# SAI_POWER_SUPPLY_BOARD.net
KiCad netlist of a schematic drawn in EAGLE
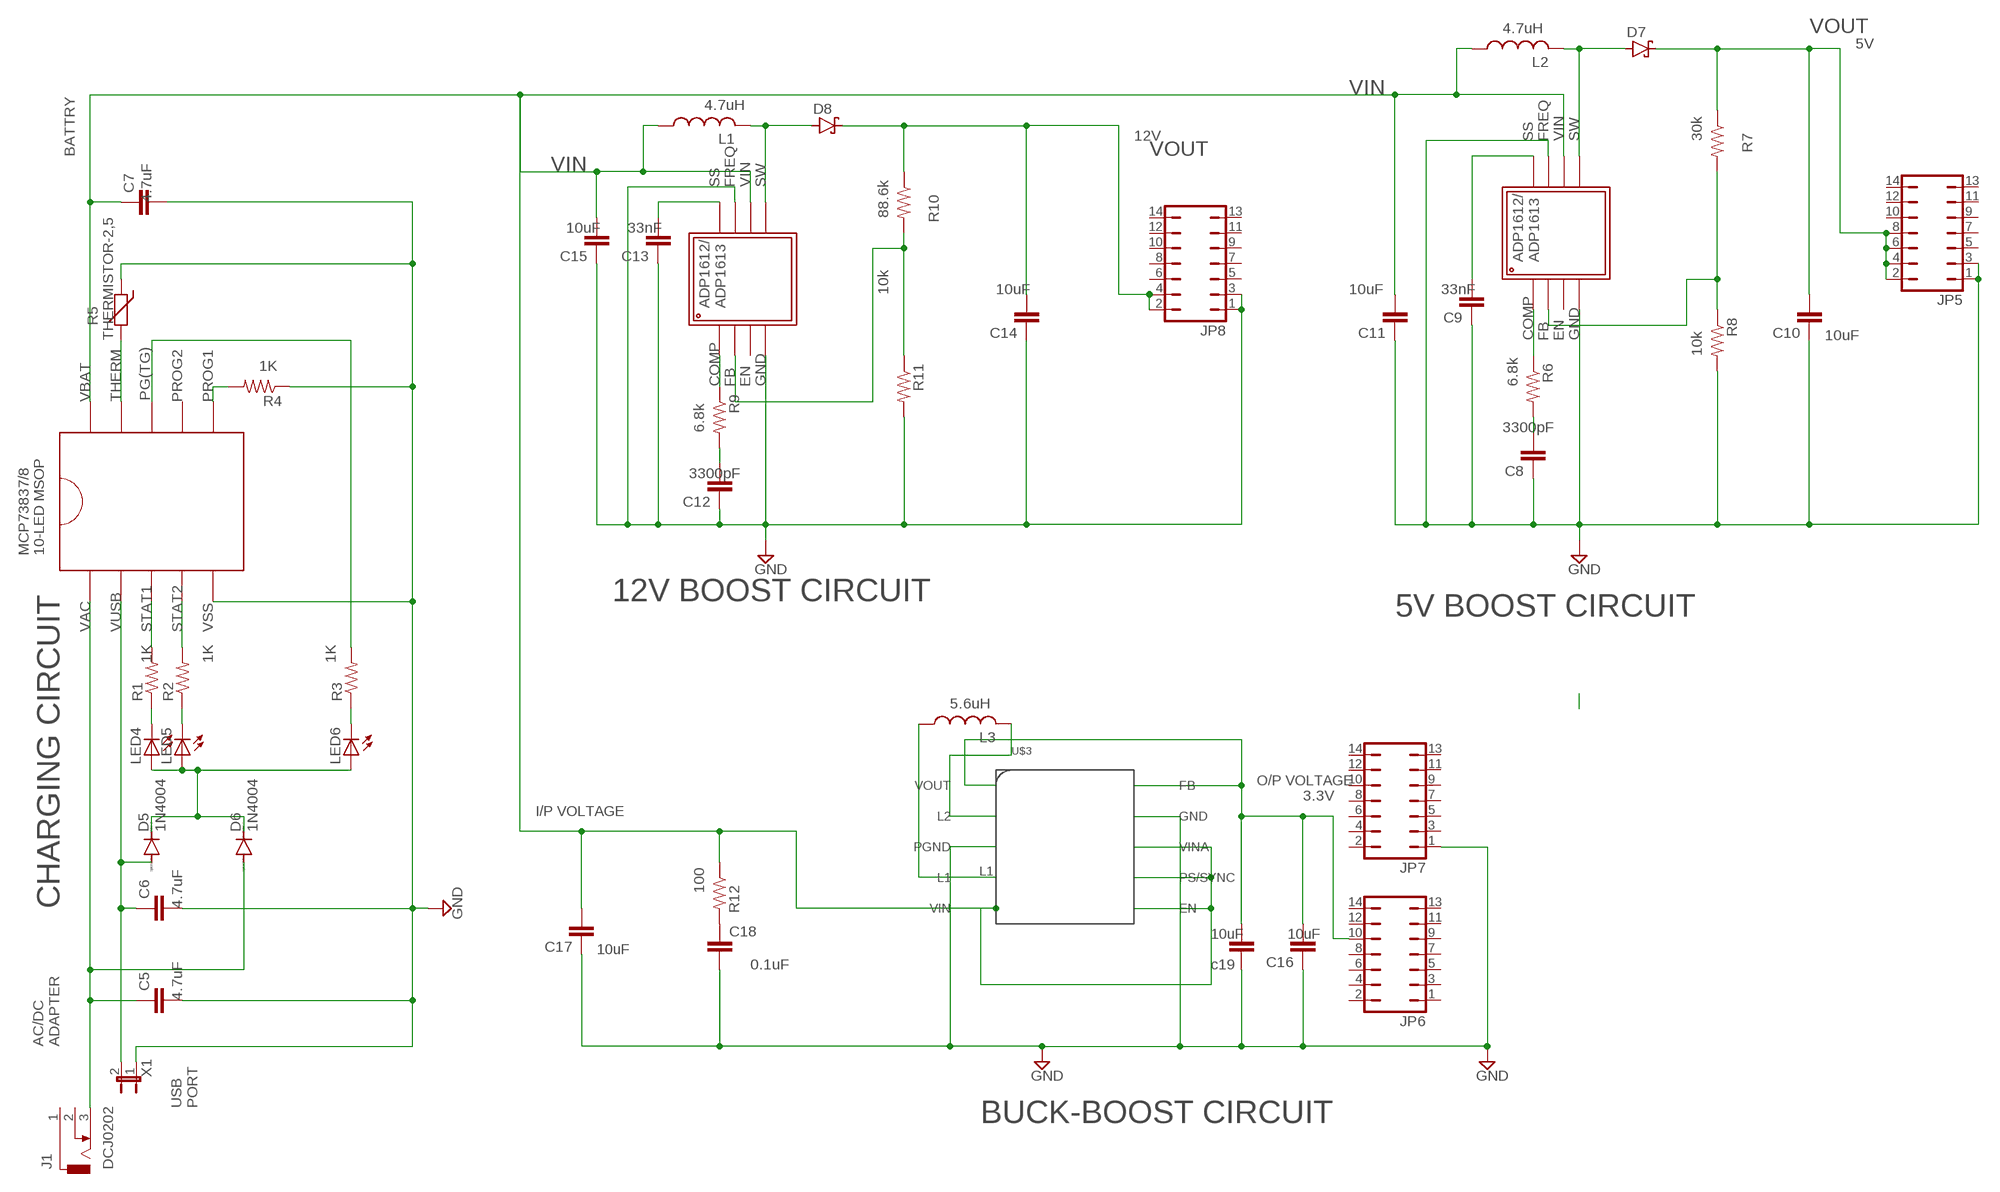
[diagram p0: schematic, sheet 1]

(export (version "E")
  (design (tool "Eeschema 10.0.6"))
  (components
    (comp (ref "C1")
      (value "C2,5-3")
      (footprint "eagle-import:C2.5-3")
      (libsource (lib "eagle-import") (part "C2,5-3"))
    )
    (comp (ref "C5")
      (value "C2.5/5")
      (footprint "eagle-import:C2.5-5")
      (libsource (lib "eagle-import") (part "C2.5/5"))
    )
    (comp (ref "C6")
      (value "C2.5/5")
      (footprint "eagle-import:C2.5-5")
      (libsource (lib "eagle-import") (part "C2.5/5"))
    )
    (comp (ref "C7")
      (value "C2.5/5")
      (footprint "eagle-import:C2.5-5")
      (libsource (lib "eagle-import") (part "C2.5/5"))
    )
    (comp (ref "C8")
      (value "C2,5-3")
      (footprint "eagle-import:C2.5-3")
      (libsource (lib "eagle-import") (part "C2,5-3"))
    )
    (comp (ref "C9")
      (value "C2,5-3")
      (footprint "eagle-import:C2.5-3")
      (libsource (lib "eagle-import") (part "C2,5-3"))
    )
    (comp (ref "C10")
      (value "C2,5-3")
      (footprint "eagle-import:C2.5-3")
      (libsource (lib "eagle-import") (part "C2,5-3"))
    )
    (comp (ref "C11")
      (value "C2,5-3")
      (footprint "eagle-import:C2.5-3")
      (libsource (lib "eagle-import") (part "C2,5-3"))
    )
    (comp (ref "C12")
      (value "C2,5-3")
      (footprint "eagle-import:C2.5-3")
      (libsource (lib "eagle-import") (part "C2,5-3"))
    )
    (comp (ref "C13")
      (value "C2,5-3")
      (footprint "eagle-import:C2.5-3")
      (libsource (lib "eagle-import") (part "C2,5-3"))
    )
    (comp (ref "C14")
      (value "C2,5-3")
      (footprint "eagle-import:C2.5-3")
      (libsource (lib "eagle-import") (part "C2,5-3"))
    )
    (comp (ref "C15")
      (value "C2,5-3")
      (footprint "eagle-import:C2.5-3")
      (libsource (lib "eagle-import") (part "C2,5-3"))
    )
    (comp (ref "C16")
      (value "C2,5-3")
      (footprint "eagle-import:C2.5-3")
      (libsource (lib "eagle-import") (part "C2,5-3"))
    )
    (comp (ref "C17")
      (value "C2,5-3")
      (footprint "eagle-import:C2.5-3")
      (libsource (lib "eagle-import") (part "C2,5-3"))
    )
    (comp (ref "C18")
      (value "C2,5-3")
      (footprint "eagle-import:C2.5-3")
      (libsource (lib "eagle-import") (part "C2,5-3"))
    )
    (comp (ref "D5")
      (value "1N4004")
      (footprint "eagle-import:DO41-10")
      (libsource (lib "eagle-import") (part "1N4004"))
    )
    (comp (ref "D6")
      (value "1N4004")
      (footprint "eagle-import:DO41-10")
      (libsource (lib "eagle-import") (part "1N4004"))
    )
    (comp (ref "D7")
      (value "SCHOTTKY-DIODEC4111-15")
      (footprint "eagle-import:C4111-15")
      (libsource (lib "eagle-import") (part "SCHOTTKY-DIODEC4111-15"))
    )
    (comp (ref "D8")
      (value "SCHOTTKY-DIODEC4111-15")
      (footprint "eagle-import:C4111-15")
      (libsource (lib "eagle-import") (part "SCHOTTKY-DIODEC4111-15"))
    )
    (comp (ref "J1")
      (value "DCJ0202")
      (footprint "eagle-import:DCJ0202")
      (libsource (lib "eagle-import") (part "DCJ0202"))
    )
    (comp (ref "JP1")
      (value "JP1E")
      (footprint "eagle-import:JP1")
      (libsource (lib "eagle-import") (part "JP1E"))
    )
    (comp (ref "JP5")
      (value "JP7Q")
      (footprint "eagle-import:JP7Q")
      (libsource (lib "eagle-import") (part "JP7Q"))
    )
    (comp (ref "JP6")
      (value "JP7Q")
      (footprint "eagle-import:JP7Q")
      (libsource (lib "eagle-import") (part "JP7Q"))
    )
    (comp (ref "JP7")
      (value "JP7Q")
      (footprint "eagle-import:JP7Q")
      (libsource (lib "eagle-import") (part "JP7Q"))
    )
    (comp (ref "JP8")
      (value "JP7Q")
      (footprint "eagle-import:JP7Q")
      (libsource (lib "eagle-import") (part "JP7Q"))
    )
    (comp (ref "L1")
      (value "L-US0204/5")
      (footprint "eagle-import:0204_5")
      (libsource (lib "eagle-import") (part "L-US0204/5"))
    )
    (comp (ref "L2")
      (value "L-US0204/5")
      (footprint "eagle-import:0204_5")
      (libsource (lib "eagle-import") (part "L-US0204/5"))
    )
    (comp (ref "L3")
      (value "L-US0204/5")
      (footprint "eagle-import:0204_5")
      (libsource (lib "eagle-import") (part "L-US0204/5"))
    )
    (comp (ref "LED4")
      (value "LED3MM")
      (footprint "eagle-import:LED3MM")
      (libsource (lib "eagle-import") (part "LED3MM"))
    )
    (comp (ref "LED5")
      (value "LED3MM")
      (footprint "eagle-import:LED3MM")
      (libsource (lib "eagle-import") (part "LED3MM"))
    )
    (comp (ref "LED6")
      (value "LED3MM")
      (footprint "eagle-import:LED3MM")
      (libsource (lib "eagle-import") (part "LED3MM"))
    )
    (comp (ref "R1")
      (value "R-US_0204/2V")
      (footprint "eagle-import:0204V")
      (libsource (lib "eagle-import") (part "R-US_0204/2V"))
    )
    (comp (ref "R2")
      (value "R-US_0204/2V")
      (footprint "eagle-import:0204V")
      (libsource (lib "eagle-import") (part "R-US_0204/2V"))
    )
    (comp (ref "R3")
      (value "R-US_0204/2V")
      (footprint "eagle-import:0204V")
      (libsource (lib "eagle-import") (part "R-US_0204/2V"))
    )
    (comp (ref "R4")
      (value "R-US_0204/2V")
      (footprint "eagle-import:0204V")
      (libsource (lib "eagle-import") (part "R-US_0204/2V"))
    )
    (comp (ref "R5")
      (value "THERMISTOR-2,5")
      (footprint "eagle-import:RS-2,5")
      (libsource (lib "eagle-import") (part "THERMISTOR-2,5"))
    )
    (comp (ref "R6")
      (value "R-US_0204/2V")
      (footprint "eagle-import:0204V")
      (libsource (lib "eagle-import") (part "R-US_0204/2V"))
    )
    (comp (ref "R7")
      (value "R-US_0204/2V")
      (footprint "eagle-import:0204V")
      (libsource (lib "eagle-import") (part "R-US_0204/2V"))
    )
    (comp (ref "R8")
      (value "R-US_0204/2V")
      (footprint "eagle-import:0204V")
      (libsource (lib "eagle-import") (part "R-US_0204/2V"))
    )
    (comp (ref "R9")
      (value "R-US_0204/2V")
      (footprint "eagle-import:0204V")
      (libsource (lib "eagle-import") (part "R-US_0204/2V"))
    )
    (comp (ref "R10")
      (value "R-US_0204/2V")
      (footprint "eagle-import:0204V")
      (libsource (lib "eagle-import") (part "R-US_0204/2V"))
    )
    (comp (ref "R11")
      (value "R-US_0204/2V")
      (footprint "eagle-import:0204V")
      (libsource (lib "eagle-import") (part "R-US_0204/2V"))
    )
    (comp (ref "R12")
      (value "R-US_0204/2V")
      (footprint "eagle-import:0204V")
      (libsource (lib "eagle-import") (part "R-US_0204/2V"))
    )
    (comp (ref "U$1")
      (value "ADP1612")
      (footprint "eagle-import:ADP1612")
      (libsource (lib "eagle-import") (part "ADP1612"))
    )
    (comp (ref "U$2")
      (value "ADP1612")
      (footprint "eagle-import:ADP1612")
      (libsource (lib "eagle-import") (part "ADP1612"))
    )
    (comp (ref "U$3")
      (value "TPS63002")
      (footprint "eagle-import:TPS63002")
      (libsource (lib "eagle-import") (part "TPS63002"))
    )
    (comp (ref "U$4")
      (value "MCP73837/8")
      (footprint "eagle-import:MCP73837_8")
      (libsource (lib "eagle-import") (part "MCP73837/8"))
    )
  )
  (nets
    (net (code "1") (name "GND") (class "Default")
      (node (ref "C1") (pin "1") (pinfunction "1_1") (pintype "passive"))
      (node (ref "C10") (pin "1") (pinfunction "1_1") (pintype "passive"))
      (node (ref "C11") (pin "1") (pinfunction "1_1") (pintype "passive"))
      (node (ref "C12") (pin "1") (pinfunction "1_1") (pintype "passive"))
      (node (ref "C13") (pin "1") (pinfunction "1_1") (pintype "passive"))
      (node (ref "C14") (pin "1") (pinfunction "1_1") (pintype "passive"))
      (node (ref "C15") (pin "1") (pinfunction "1_1") (pintype "passive"))
      (node (ref "C16") (pin "1") (pinfunction "1_1") (pintype "passive"))
      (node (ref "C17") (pin "1") (pinfunction "1_1") (pintype "passive"))
      (node (ref "C18") (pin "2") (pinfunction "2_2") (pintype "passive"))
      (node (ref "C5") (pin "2") (pinfunction "2_2") (pintype "passive"))
      (node (ref "C6") (pin "2") (pinfunction "2_2") (pintype "passive"))
      (node (ref "C7") (pin "2") (pinfunction "2_2") (pintype "passive"))
      (node (ref "C8") (pin "1") (pinfunction "1_1") (pintype "passive"))
      (node (ref "C9") (pin "1") (pinfunction "1_1") (pintype "passive"))
      (node (ref "JP1") (pin "1") (pinfunction "1_1") (pintype "passive"))
      (node (ref "JP5") (pin "1") (pinfunction "1_1") (pintype "passive"))
      (node (ref "JP5") (pin "3") (pinfunction "3_3") (pintype "passive"))
      (node (ref "JP7") (pin "1") (pinfunction "1_1") (pintype "passive"))
      (node (ref "JP8") (pin "1") (pinfunction "1_1") (pintype "passive"))
      (node (ref "JP8") (pin "3") (pinfunction "3_3") (pintype "passive"))
      (node (ref "R11") (pin "2") (pinfunction "2_2") (pintype "passive"))
      (node (ref "R4") (pin "1") (pinfunction "1_1") (pintype "passive"))
      (node (ref "R5") (pin "1") (pinfunction "1_1") (pintype "passive"))
      (node (ref "R8") (pin "2") (pinfunction "2_2") (pintype "passive"))
      (node (ref "U$1") (pin "P$4") (pinfunction "P$4_P$4") (pintype "bidirectional"))
      (node (ref "U$1") (pin "P$6") (pinfunction "P$6_P$6") (pintype "bidirectional"))
      (node (ref "U$2") (pin "P$4") (pinfunction "P$4_P$4") (pintype "bidirectional"))
      (node (ref "U$2") (pin "P$6") (pinfunction "P$6_P$6") (pintype "bidirectional"))
      (node (ref "U$3") (pin "GND") (pinfunction "GND_GND") (pintype "bidirectional"))
      (node (ref "U$3") (pin "PGND") (pinfunction "PGND_PGND") (pintype "bidirectional"))
      (node (ref "U$4") (pin "P$5") (pinfunction "P$5_P$5") (pintype "bidirectional"))
    )
    (net (code "2") (name "Net-(C1-Pad2)") (class "Default")
      (node (ref "C1") (pin "2") (pinfunction "2_2") (pintype "passive"))
      (node (ref "C16") (pin "2") (pinfunction "2_2") (pintype "passive"))
      (node (ref "JP6") (pin "10") (pinfunction "10_10") (pintype "passive"))
      (node (ref "U$3") (pin "FB") (pinfunction "FB_FB") (pintype "bidirectional"))
      (node (ref "U$3") (pin "VOUT") (pinfunction "VOUT_VOUT") (pintype "bidirectional"))
    )
    (net (code "3") (name "Net-(C5-Pad1)") (class "Default")
      (node (ref "C5") (pin "1") (pinfunction "1_1") (pintype "passive"))
      (node (ref "D6") (pin "A") (pinfunction "A_A") (pintype "passive"))
      (node (ref "J1") (pin "3") (pinfunction "3_3") (pintype "passive"))
      (node (ref "U$4") (pin "P$1") (pinfunction "P$1_P$1") (pintype "bidirectional"))
    )
    (net (code "4") (name "Net-(C6-Pad1)") (class "Default")
      (node (ref "C6") (pin "1") (pinfunction "1_1") (pintype "passive"))
      (node (ref "D5") (pin "A") (pinfunction "A_A") (pintype "passive"))
      (node (ref "JP1") (pin "2") (pinfunction "2_2") (pintype "passive"))
      (node (ref "U$4") (pin "P$2") (pinfunction "P$2_P$2") (pintype "bidirectional"))
    )
    (net (code "5") (name "Net-(C8-Pad2)") (class "Default")
      (node (ref "C8") (pin "2") (pinfunction "2_2") (pintype "passive"))
      (node (ref "R6") (pin "2") (pinfunction "2_2") (pintype "passive"))
    )
    (net (code "6") (name "Net-(C9-Pad2)") (class "Default")
      (node (ref "C9") (pin "2") (pinfunction "2_2") (pintype "passive"))
      (node (ref "U$1") (pin "P$5") (pinfunction "P$5_P$5") (pintype "bidirectional"))
    )
    (net (code "7") (name "Net-(C10-Pad2)") (class "Default")
      (node (ref "C10") (pin "2") (pinfunction "2_2") (pintype "passive"))
      (node (ref "D7") (pin "C") (pinfunction "C_C") (pintype "passive"))
      (node (ref "JP5") (pin "2") (pinfunction "2_2") (pintype "passive"))
      (node (ref "JP5") (pin "4") (pinfunction "4_4") (pintype "passive"))
      (node (ref "JP5") (pin "6") (pinfunction "6_6") (pintype "passive"))
      (node (ref "JP5") (pin "8") (pinfunction "8_8") (pintype "passive"))
      (node (ref "R7") (pin "1") (pinfunction "1_1") (pintype "passive"))
    )
    (net (code "8") (name "Net-(C11-Pad2)") (class "Default")
      (node (ref "C11") (pin "2") (pinfunction "2_2") (pintype "passive"))
      (node (ref "C15") (pin "2") (pinfunction "2_2") (pintype "passive"))
      (node (ref "C17") (pin "2") (pinfunction "2_2") (pintype "passive"))
      (node (ref "C7") (pin "1") (pinfunction "1_1") (pintype "passive"))
      (node (ref "L1") (pin "1") (pinfunction "1_1") (pintype "passive"))
      (node (ref "L2") (pin "1") (pinfunction "1_1") (pintype "passive"))
      (node (ref "R12") (pin "1") (pinfunction "1_1") (pintype "passive"))
      (node (ref "U$1") (pin "P$7") (pinfunction "P$7_P$7") (pintype "bidirectional"))
      (node (ref "U$2") (pin "P$7") (pinfunction "P$7_P$7") (pintype "bidirectional"))
      (node (ref "U$3") (pin "EN") (pinfunction "EN_EN") (pintype "bidirectional"))
      (node (ref "U$3") (pin "PS/SYNC") (pinfunction "PS/SYNC_PS/SYNC") (pintype "bidirectional"))
      (node (ref "U$3") (pin "VIN") (pinfunction "VIN_VIN") (pintype "bidirectional"))
      (node (ref "U$3") (pin "VINA") (pinfunction "VINA_VINA") (pintype "bidirectional"))
      (node (ref "U$4") (pin "P$10") (pinfunction "P$10_P$10") (pintype "bidirectional"))
    )
    (net (code "9") (name "Net-(C12-Pad2)") (class "Default")
      (node (ref "C12") (pin "2") (pinfunction "2_2") (pintype "passive"))
      (node (ref "R9") (pin "2") (pinfunction "2_2") (pintype "passive"))
    )
    (net (code "10") (name "Net-(C13-Pad2)") (class "Default")
      (node (ref "C13") (pin "2") (pinfunction "2_2") (pintype "passive"))
      (node (ref "U$2") (pin "P$5") (pinfunction "P$5_P$5") (pintype "bidirectional"))
    )
    (net (code "11") (name "Net-(C14-Pad2)") (class "Default")
      (node (ref "C14") (pin "2") (pinfunction "2_2") (pintype "passive"))
      (node (ref "D8") (pin "C") (pinfunction "C_C") (pintype "passive"))
      (node (ref "JP8") (pin "2") (pinfunction "2_2") (pintype "passive"))
      (node (ref "JP8") (pin "4") (pinfunction "4_4") (pintype "passive"))
      (node (ref "R10") (pin "1") (pinfunction "1_1") (pintype "passive"))
    )
    (net (code "12") (name "Net-(C18-Pad1)") (class "Default")
      (node (ref "C18") (pin "1") (pinfunction "1_1") (pintype "passive"))
      (node (ref "R12") (pin "2") (pinfunction "2_2") (pintype "passive"))
    )
    (net (code "13") (name "Net-(D5-PadC)") (class "Default")
      (node (ref "D5") (pin "C") (pinfunction "C_C") (pintype "passive"))
      (node (ref "D6") (pin "C") (pinfunction "C_C") (pintype "passive"))
      (node (ref "LED4") (pin "A") (pinfunction "A_A") (pintype "passive"))
      (node (ref "LED5") (pin "A") (pinfunction "A_A") (pintype "passive"))
      (node (ref "LED6") (pin "A") (pinfunction "A_A") (pintype "passive"))
    )
    (net (code "14") (name "Net-(D7-PadA)") (class "Default")
      (node (ref "D7") (pin "A") (pinfunction "A_A") (pintype "passive"))
      (node (ref "L2") (pin "2") (pinfunction "2_2") (pintype "passive"))
      (node (ref "U$1") (pin "P$8") (pinfunction "P$8_P$8") (pintype "bidirectional"))
    )
    (net (code "15") (name "Net-(D8-PadA)") (class "Default")
      (node (ref "D8") (pin "A") (pinfunction "A_A") (pintype "passive"))
      (node (ref "L1") (pin "2") (pinfunction "2_2") (pintype "passive"))
      (node (ref "U$2") (pin "P$8") (pinfunction "P$8_P$8") (pintype "bidirectional"))
    )
    (net (code "16") (name "Net-(L3-Pad1)") (class "Default")
      (node (ref "L3") (pin "1") (pinfunction "1_1") (pintype "passive"))
      (node (ref "U$3") (pin "L1") (pinfunction "L1_L1") (pintype "bidirectional"))
    )
    (net (code "17") (name "Net-(L3-Pad2)") (class "Default")
      (node (ref "L3") (pin "2") (pinfunction "2_2") (pintype "passive"))
      (node (ref "U$3") (pin "L2") (pinfunction "L2_L2") (pintype "bidirectional"))
    )
    (net (code "18") (name "Net-(LED4-C)") (class "Default")
      (node (ref "LED4") (pin "K") (pinfunction "C_K") (pintype "passive"))
      (node (ref "R1") (pin "1") (pinfunction "1_1") (pintype "passive"))
    )
    (net (code "19") (name "Net-(LED5-C)") (class "Default")
      (node (ref "LED5") (pin "K") (pinfunction "C_K") (pintype "passive"))
      (node (ref "R2") (pin "1") (pinfunction "1_1") (pintype "passive"))
    )
    (net (code "20") (name "Net-(LED6-C)") (class "Default")
      (node (ref "LED6") (pin "K") (pinfunction "C_K") (pintype "passive"))
      (node (ref "R3") (pin "1") (pinfunction "1_1") (pintype "passive"))
    )
    (net (code "21") (name "Net-(R1-Pad2)") (class "Default")
      (node (ref "R1") (pin "2") (pinfunction "2_2") (pintype "passive"))
      (node (ref "U$4") (pin "P$3") (pinfunction "P$3_P$3") (pintype "bidirectional"))
    )
    (net (code "22") (name "Net-(R2-Pad2)") (class "Default")
      (node (ref "R2") (pin "2") (pinfunction "2_2") (pintype "passive"))
      (node (ref "U$4") (pin "P$4") (pinfunction "P$4_P$4") (pintype "bidirectional"))
    )
    (net (code "23") (name "Net-(R3-Pad2)") (class "Default")
      (node (ref "R3") (pin "2") (pinfunction "2_2") (pintype "passive"))
      (node (ref "U$4") (pin "P$8") (pinfunction "P$8_P$8") (pintype "bidirectional"))
    )
    (net (code "24") (name "Net-(R4-Pad2)") (class "Default")
      (node (ref "R4") (pin "2") (pinfunction "2_2") (pintype "passive"))
      (node (ref "U$4") (pin "P$6") (pinfunction "P$6_P$6") (pintype "bidirectional"))
    )
    (net (code "25") (name "Net-(R5-Pad2)") (class "Default")
      (node (ref "R5") (pin "2") (pinfunction "2_2") (pintype "passive"))
      (node (ref "U$4") (pin "P$9") (pinfunction "P$9_P$9") (pintype "bidirectional"))
    )
    (net (code "26") (name "Net-(R6-Pad1)") (class "Default")
      (node (ref "R6") (pin "1") (pinfunction "1_1") (pintype "passive"))
      (node (ref "U$1") (pin "P$1") (pinfunction "P$1_P$1") (pintype "bidirectional"))
    )
    (net (code "27") (name "Net-(R7-Pad2)") (class "Default")
      (node (ref "R7") (pin "2") (pinfunction "2_2") (pintype "passive"))
      (node (ref "R8") (pin "1") (pinfunction "1_1") (pintype "passive"))
      (node (ref "U$1") (pin "P$2") (pinfunction "P$2_P$2") (pintype "bidirectional"))
    )
    (net (code "28") (name "Net-(R9-Pad1)") (class "Default")
      (node (ref "R9") (pin "1") (pinfunction "1_1") (pintype "passive"))
      (node (ref "U$2") (pin "P$1") (pinfunction "P$1_P$1") (pintype "bidirectional"))
    )
    (net (code "29") (name "Net-(R10-Pad2)") (class "Default")
      (node (ref "R10") (pin "2") (pinfunction "2_2") (pintype "passive"))
      (node (ref "R11") (pin "1") (pinfunction "1_1") (pintype "passive"))
      (node (ref "U$2") (pin "P$2") (pinfunction "P$2_P$2") (pintype "bidirectional"))
    )
    (net (code "30") (name "unconnected-(J1-Pad1)") (class "Default")
      (node (ref "J1") (pin "1") (pinfunction "1_1") (pintype "passive"))
    )
    (net (code "31") (name "unconnected-(J1-Pad2)") (class "Default")
      (node (ref "J1") (pin "2") (pinfunction "2_2") (pintype "passive"))
    )
    (net (code "32") (name "unconnected-(JP5-Pad5)") (class "Default")
      (node (ref "JP5") (pin "5") (pinfunction "5_5") (pintype "passive"))
    )
    (net (code "33") (name "unconnected-(JP5-Pad7)") (class "Default")
      (node (ref "JP5") (pin "7") (pinfunction "7_7") (pintype "passive"))
    )
    (net (code "34") (name "unconnected-(JP5-Pad9)") (class "Default")
      (node (ref "JP5") (pin "9") (pinfunction "9_9") (pintype "passive"))
    )
    (net (code "35") (name "unconnected-(JP5-Pad10)") (class "Default")
      (node (ref "JP5") (pin "10") (pinfunction "10_10") (pintype "passive"))
    )
    (net (code "36") (name "unconnected-(JP5-Pad11)") (class "Default")
      (node (ref "JP5") (pin "11") (pinfunction "11_11") (pintype "passive"))
    )
    (net (code "37") (name "unconnected-(JP5-Pad12)") (class "Default")
      (node (ref "JP5") (pin "12") (pinfunction "12_12") (pintype "passive"))
    )
    (net (code "38") (name "unconnected-(JP5-Pad13)") (class "Default")
      (node (ref "JP5") (pin "13") (pinfunction "13_13") (pintype "passive"))
    )
    (net (code "39") (name "unconnected-(JP5-Pad14)") (class "Default")
      (node (ref "JP5") (pin "14") (pinfunction "14_14") (pintype "passive"))
    )
    (net (code "40") (name "unconnected-(JP6-Pad1)") (class "Default")
      (node (ref "JP6") (pin "1") (pinfunction "1_1") (pintype "passive"))
    )
    (net (code "41") (name "unconnected-(JP6-Pad2)") (class "Default")
      (node (ref "JP6") (pin "2") (pinfunction "2_2") (pintype "passive"))
    )
    (net (code "42") (name "unconnected-(JP6-Pad3)") (class "Default")
      (node (ref "JP6") (pin "3") (pinfunction "3_3") (pintype "passive"))
    )
    (net (code "43") (name "unconnected-(JP6-Pad4)") (class "Default")
      (node (ref "JP6") (pin "4") (pinfunction "4_4") (pintype "passive"))
    )
    (net (code "44") (name "unconnected-(JP6-Pad5)") (class "Default")
      (node (ref "JP6") (pin "5") (pinfunction "5_5") (pintype "passive"))
    )
    (net (code "45") (name "unconnected-(JP6-Pad6)") (class "Default")
      (node (ref "JP6") (pin "6") (pinfunction "6_6") (pintype "passive"))
    )
    (net (code "46") (name "unconnected-(JP6-Pad7)") (class "Default")
      (node (ref "JP6") (pin "7") (pinfunction "7_7") (pintype "passive"))
    )
    (net (code "47") (name "unconnected-(JP6-Pad8)") (class "Default")
      (node (ref "JP6") (pin "8") (pinfunction "8_8") (pintype "passive"))
    )
    (net (code "48") (name "unconnected-(JP6-Pad9)") (class "Default")
      (node (ref "JP6") (pin "9") (pinfunction "9_9") (pintype "passive"))
    )
    (net (code "49") (name "unconnected-(JP6-Pad11)") (class "Default")
      (node (ref "JP6") (pin "11") (pinfunction "11_11") (pintype "passive"))
    )
    (net (code "50") (name "unconnected-(JP6-Pad12)") (class "Default")
      (node (ref "JP6") (pin "12") (pinfunction "12_12") (pintype "passive"))
    )
    (net (code "51") (name "unconnected-(JP6-Pad13)") (class "Default")
      (node (ref "JP6") (pin "13") (pinfunction "13_13") (pintype "passive"))
    )
    (net (code "52") (name "unconnected-(JP6-Pad14)") (class "Default")
      (node (ref "JP6") (pin "14") (pinfunction "14_14") (pintype "passive"))
    )
    (net (code "53") (name "unconnected-(JP7-Pad2)") (class "Default")
      (node (ref "JP7") (pin "2") (pinfunction "2_2") (pintype "passive"))
    )
    (net (code "54") (name "unconnected-(JP7-Pad3)") (class "Default")
      (node (ref "JP7") (pin "3") (pinfunction "3_3") (pintype "passive"))
    )
    (net (code "55") (name "unconnected-(JP7-Pad4)") (class "Default")
      (node (ref "JP7") (pin "4") (pinfunction "4_4") (pintype "passive"))
    )
    (net (code "56") (name "unconnected-(JP7-Pad5)") (class "Default")
      (node (ref "JP7") (pin "5") (pinfunction "5_5") (pintype "passive"))
    )
    (net (code "57") (name "unconnected-(JP7-Pad6)") (class "Default")
      (node (ref "JP7") (pin "6") (pinfunction "6_6") (pintype "passive"))
    )
    (net (code "58") (name "unconnected-(JP7-Pad7)") (class "Default")
      (node (ref "JP7") (pin "7") (pinfunction "7_7") (pintype "passive"))
    )
    (net (code "59") (name "unconnected-(JP7-Pad8)") (class "Default")
      (node (ref "JP7") (pin "8") (pinfunction "8_8") (pintype "passive"))
    )
    (net (code "60") (name "unconnected-(JP7-Pad9)") (class "Default")
      (node (ref "JP7") (pin "9") (pinfunction "9_9") (pintype "passive"))
    )
    (net (code "61") (name "unconnected-(JP7-Pad10)") (class "Default")
      (node (ref "JP7") (pin "10") (pinfunction "10_10") (pintype "passive"))
    )
    (net (code "62") (name "unconnected-(JP7-Pad11)") (class "Default")
      (node (ref "JP7") (pin "11") (pinfunction "11_11") (pintype "passive"))
    )
    (net (code "63") (name "unconnected-(JP7-Pad12)") (class "Default")
      (node (ref "JP7") (pin "12") (pinfunction "12_12") (pintype "passive"))
    )
    (net (code "64") (name "unconnected-(JP7-Pad13)") (class "Default")
      (node (ref "JP7") (pin "13") (pinfunction "13_13") (pintype "passive"))
    )
    (net (code "65") (name "unconnected-(JP7-Pad14)") (class "Default")
      (node (ref "JP7") (pin "14") (pinfunction "14_14") (pintype "passive"))
    )
    (net (code "66") (name "unconnected-(JP8-Pad5)") (class "Default")
      (node (ref "JP8") (pin "5") (pinfunction "5_5") (pintype "passive"))
    )
    (net (code "67") (name "unconnected-(JP8-Pad6)") (class "Default")
      (node (ref "JP8") (pin "6") (pinfunction "6_6") (pintype "passive"))
    )
    (net (code "68") (name "unconnected-(JP8-Pad7)") (class "Default")
      (node (ref "JP8") (pin "7") (pinfunction "7_7") (pintype "passive"))
    )
    (net (code "69") (name "unconnected-(JP8-Pad8)") (class "Default")
      (node (ref "JP8") (pin "8") (pinfunction "8_8") (pintype "passive"))
    )
    (net (code "70") (name "unconnected-(JP8-Pad9)") (class "Default")
      (node (ref "JP8") (pin "9") (pinfunction "9_9") (pintype "passive"))
    )
    (net (code "71") (name "unconnected-(JP8-Pad10)") (class "Default")
      (node (ref "JP8") (pin "10") (pinfunction "10_10") (pintype "passive"))
    )
    (net (code "72") (name "unconnected-(JP8-Pad11)") (class "Default")
      (node (ref "JP8") (pin "11") (pinfunction "11_11") (pintype "passive"))
    )
    (net (code "73") (name "unconnected-(JP8-Pad12)") (class "Default")
      (node (ref "JP8") (pin "12") (pinfunction "12_12") (pintype "passive"))
    )
    (net (code "74") (name "unconnected-(JP8-Pad13)") (class "Default")
      (node (ref "JP8") (pin "13") (pinfunction "13_13") (pintype "passive"))
    )
    (net (code "75") (name "unconnected-(JP8-Pad14)") (class "Default")
      (node (ref "JP8") (pin "14") (pinfunction "14_14") (pintype "passive"))
    )
    (net (code "76") (name "unconnected-(U$1-PadP$3)") (class "Default")
      (node (ref "U$1") (pin "P$3") (pinfunction "P$3_P$3") (pintype "bidirectional"))
    )
    (net (code "77") (name "unconnected-(U$2-PadP$3)") (class "Default")
      (node (ref "U$2") (pin "P$3") (pinfunction "P$3_P$3") (pintype "bidirectional"))
    )
    (net (code "78") (name "unconnected-(U$4-PadP$7)") (class "Default")
      (node (ref "U$4") (pin "P$7") (pinfunction "P$7_P$7") (pintype "bidirectional"))
    )
  )
)
